# opensda-shield.net
KiCad netlist of a schematic drawn in EAGLE
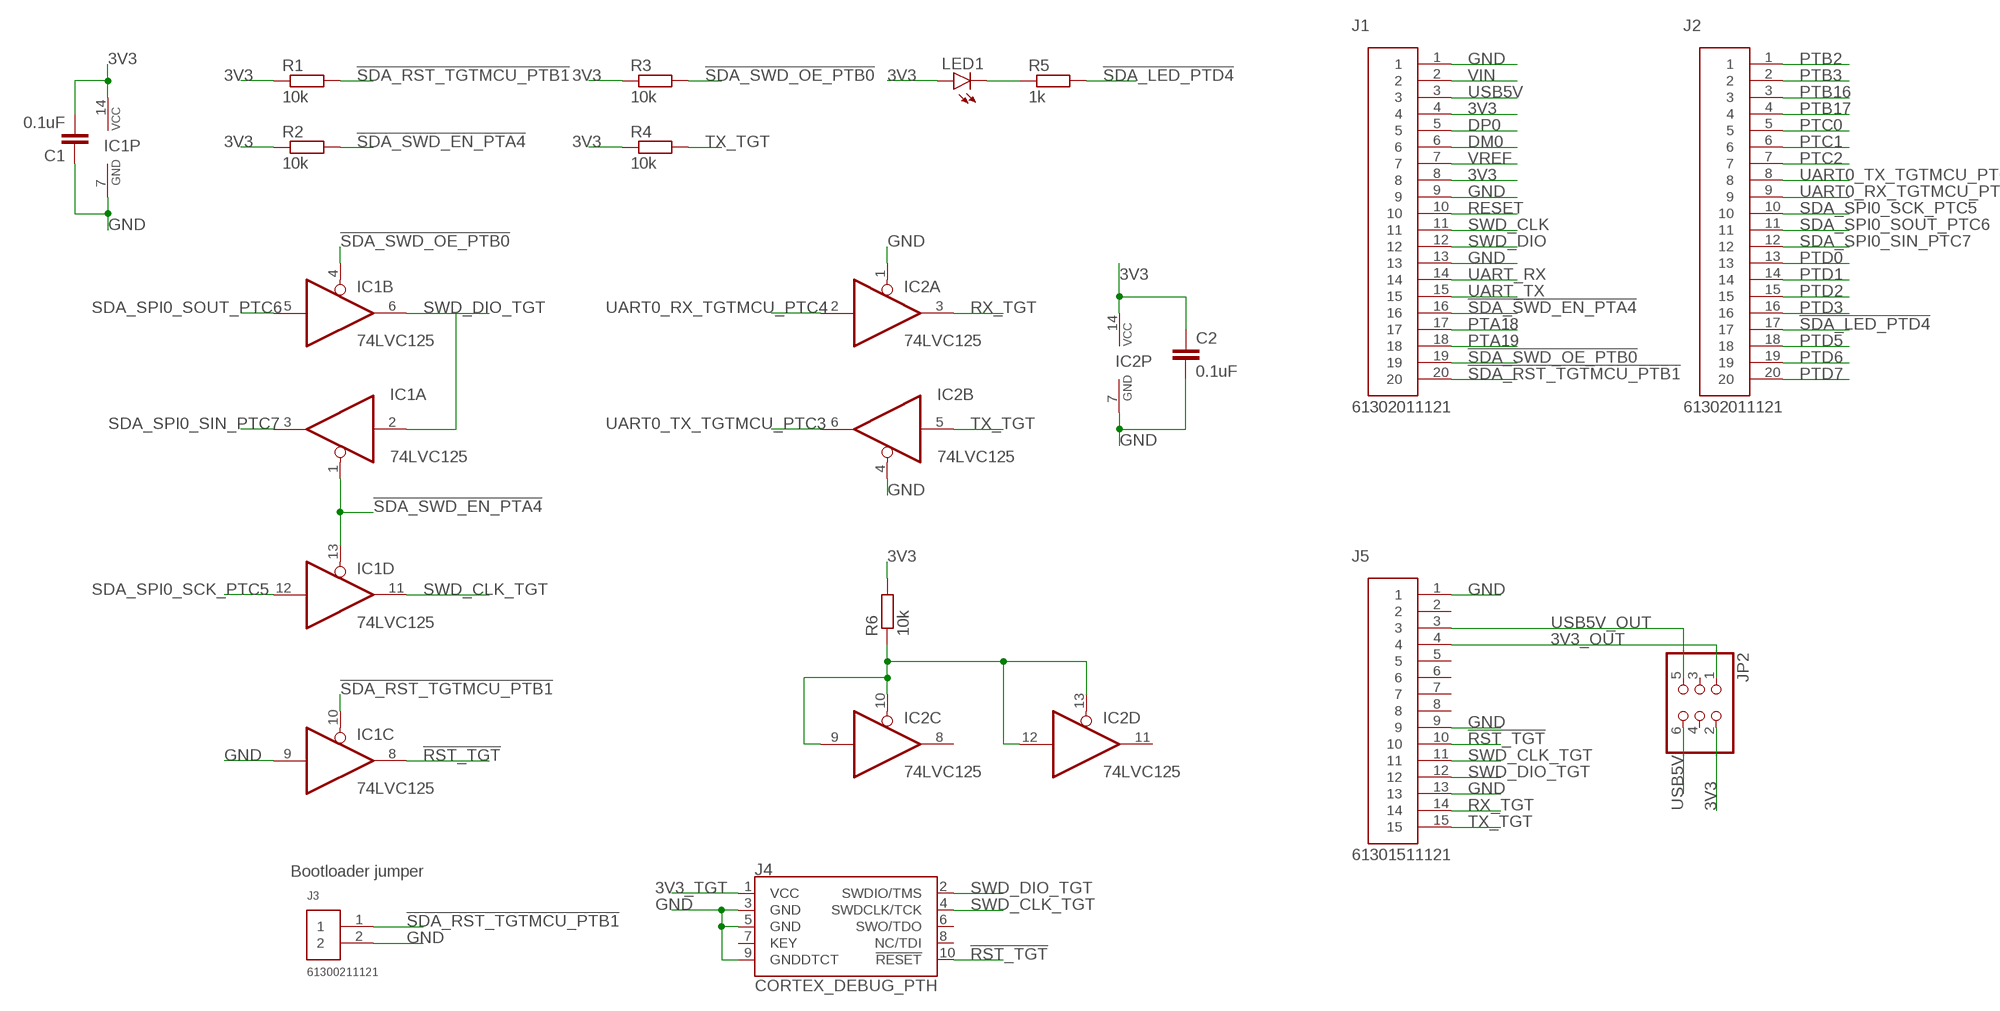
[diagram p0: schematic, sheet 1]

(export (version "E")
  (design (tool "Eeschema 10.0.6"))
  (components
    (comp (ref "C1")
      (value "0.1uF")
      (footprint "eagle-import:C0805")
      (libsource (lib "eagle-import") (part "C-EUC0805"))
    )
    (comp (ref "C2")
      (value "0.1uF")
      (footprint "eagle-import:C0805")
      (libsource (lib "eagle-import") (part "C-EUC0805"))
    )
    (comp (ref "IC1")
      (value "74LVC125")
      (footprint "eagle-import:TSSOP14")
      (libsource (lib "eagle-import") (part "74125PWABT"))
    )
    (comp (ref "IC2")
      (value "74LVC125")
      (footprint "eagle-import:TSSOP14")
      (libsource (lib "eagle-import") (part "74125PWABT"))
    )
    (comp (ref "J1")
      (value "61302011121")
      (footprint "eagle-import:61302011121")
      (fields
        (field (name "DIGIKEY_PART_NUMBER") "732-5329-ND")
        (field (name "MANUFACTURER") "Wurth Electronics Inc.")
        (field (name "CREATED_BY") "PCBLayout.com")
      )
      (libsource (lib "eagle-import") (part "61302011121"))
    )
    (comp (ref "J2")
      (value "61302011121")
      (footprint "eagle-import:61302011121")
      (fields
        (field (name "DIGIKEY_PART_NUMBER") "732-5329-ND")
        (field (name "MANUFACTURER") "Wurth Electronics Inc.")
        (field (name "CREATED_BY") "PCBLayout.com")
      )
      (libsource (lib "eagle-import") (part "61302011121"))
    )
    (comp (ref "J3")
      (value "61300211121")
      (footprint "eagle-import:61300211121")
      (fields
        (field (name "DIGI_KEY_PART_NUMBER") "732-5315-ND")
        (field (name "MANUFACTURER") "Wurth Electronics Inc.")
        (field (name "CREATED_BY") "PCBLayout.com")
      )
      (libsource (lib "eagle-import") (part "61300211121"))
    )
    (comp (ref "J4")
      (value "CORTEX_DEBUG_PTH")
      (footprint "eagle-import:2X5-PTH-1.27MM")
      (libsource (lib "eagle-import") (part "CORTEX_DEBUG_PTH"))
    )
    (comp (ref "J5")
      (value "61301511121")
      (footprint "eagle-import:61301511121")
      (fields
        (field (name "DIGIKEY_PART_NUMBER") "732-5326-ND")
        (field (name "MANUFACTURER") "Wurth Electronics Inc.")
        (field (name "CREATED_BY") "PCBLayout.com")
      )
      (libsource (lib "eagle-import") (part "61301511121"))
    )
    (comp (ref "JP2")
      (value "PINHD-2X3")
      (footprint "eagle-import:2X03")
      (libsource (lib "eagle-import") (part "PINHD-2X3"))
    )
    (comp (ref "LED1")
      (value "LEDCHIPLED_0805")
      (footprint "eagle-import:CHIPLED_0805")
      (libsource (lib "eagle-import") (part "LEDCHIPLED_0805"))
    )
    (comp (ref "R1")
      (value "10k")
      (footprint "eagle-import:R0805")
      (libsource (lib "eagle-import") (part "R-EU_R0805"))
    )
    (comp (ref "R2")
      (value "10k")
      (footprint "eagle-import:R0805")
      (libsource (lib "eagle-import") (part "R-EU_R0805"))
    )
    (comp (ref "R3")
      (value "10k")
      (footprint "eagle-import:R0805")
      (libsource (lib "eagle-import") (part "R-EU_R0805"))
    )
    (comp (ref "R4")
      (value "10k")
      (footprint "eagle-import:R0805")
      (libsource (lib "eagle-import") (part "R-EU_R0805"))
    )
    (comp (ref "R5")
      (value "1k")
      (footprint "eagle-import:R0805")
      (libsource (lib "eagle-import") (part "R-EU_R0805"))
    )
    (comp (ref "R6")
      (value "10k")
      (footprint "eagle-import:R0805")
      (libsource (lib "eagle-import") (part "R-EU_R0805"))
    )
  )
  (nets
    (net (code "1") (name "/3V3") (class "Default")
      (node (ref "C1") (pin "2") (pinfunction "2_2") (pintype "passive"))
      (node (ref "C2") (pin "1") (pinfunction "1_1") (pintype "passive"))
      (node (ref "IC1") (pin "14") (pinfunction "VCC_14") (pintype "power_in"))
      (node (ref "IC2") (pin "14") (pinfunction "VCC_14") (pintype "power_in"))
      (node (ref "J1") (pin "4") (pinfunction "4_4") (pintype "passive"))
      (node (ref "J1") (pin "8") (pinfunction "8_8") (pintype "passive"))
      (node (ref "JP2") (pin "2") (pinfunction "2_2") (pintype "passive"))
      (node (ref "LED1") (pin "A") (pinfunction "A_A") (pintype "passive"))
      (node (ref "R1") (pin "1") (pinfunction "1_1") (pintype "passive"))
      (node (ref "R2") (pin "1") (pinfunction "1_1") (pintype "passive"))
      (node (ref "R3") (pin "1") (pinfunction "1_1") (pintype "passive"))
      (node (ref "R4") (pin "1") (pinfunction "1_1") (pintype "passive"))
      (node (ref "R6") (pin "2") (pinfunction "2_2") (pintype "passive"))
    )
    (net (code "2") (name "/3V3_OUT") (class "Default")
      (node (ref "J5") (pin "4") (pinfunction "4_4") (pintype "passive"))
      (node (ref "JP2") (pin "1") (pinfunction "1_1") (pintype "passive"))
    )
    (net (code "3") (name "/3V3_TGT") (class "Default")
      (node (ref "J4") (pin "1") (pinfunction "VCC_1") (pintype "bidirectional"))
    )
    (net (code "4") (name "/DM0") (class "Default")
      (node (ref "J1") (pin "6") (pinfunction "6_6") (pintype "passive"))
    )
    (net (code "5") (name "/DP0") (class "Default")
      (node (ref "J1") (pin "5") (pinfunction "5_5") (pintype "passive"))
    )
    (net (code "6") (name "/GND") (class "Default")
      (node (ref "C1") (pin "1") (pinfunction "1_1") (pintype "passive"))
      (node (ref "C2") (pin "2") (pinfunction "2_2") (pintype "passive"))
      (node (ref "IC1") (pin "7") (pinfunction "GND_7") (pintype "power_in"))
      (node (ref "IC1") (pin "9") (pinfunction "I_9") (pintype "input"))
      (node (ref "IC2") (pin "1") (pinfunction "OE_1") (pintype "input"))
      (node (ref "IC2") (pin "4") (pinfunction "OE_4") (pintype "input"))
      (node (ref "IC2") (pin "7") (pinfunction "GND_7") (pintype "power_in"))
      (node (ref "J1") (pin "1") (pinfunction "1_1") (pintype "passive"))
      (node (ref "J1") (pin "13") (pinfunction "13_13") (pintype "passive"))
      (node (ref "J1") (pin "9") (pinfunction "9_9") (pintype "passive"))
      (node (ref "J3") (pin "2") (pinfunction "2_2") (pintype "passive"))
      (node (ref "J4") (pin "3") (pinfunction "GND_3") (pintype "bidirectional"))
      (node (ref "J4") (pin "5") (pinfunction "GND_5") (pintype "bidirectional"))
      (node (ref "J4") (pin "9") (pinfunction "GNDDTCT_9") (pintype "bidirectional"))
      (node (ref "J5") (pin "1") (pinfunction "1_1") (pintype "passive"))
      (node (ref "J5") (pin "13") (pinfunction "13_13") (pintype "passive"))
      (node (ref "J5") (pin "9") (pinfunction "9_9") (pintype "passive"))
    )
    (net (code "7") (name "/PTA18") (class "Default")
      (node (ref "J1") (pin "17") (pinfunction "17_17") (pintype "passive"))
    )
    (net (code "8") (name "/PTA19") (class "Default")
      (node (ref "J1") (pin "18") (pinfunction "18_18") (pintype "passive"))
    )
    (net (code "9") (name "/PTB2") (class "Default")
      (node (ref "J2") (pin "1") (pinfunction "1_1") (pintype "passive"))
    )
    (net (code "10") (name "/PTB3") (class "Default")
      (node (ref "J2") (pin "2") (pinfunction "2_2") (pintype "passive"))
    )
    (net (code "11") (name "/PTB16") (class "Default")
      (node (ref "J2") (pin "3") (pinfunction "3_3") (pintype "passive"))
    )
    (net (code "12") (name "/PTB17") (class "Default")
      (node (ref "J2") (pin "4") (pinfunction "4_4") (pintype "passive"))
    )
    (net (code "13") (name "/PTC0") (class "Default")
      (node (ref "J2") (pin "5") (pinfunction "5_5") (pintype "passive"))
    )
    (net (code "14") (name "/PTC1") (class "Default")
      (node (ref "J2") (pin "6") (pinfunction "6_6") (pintype "passive"))
    )
    (net (code "15") (name "/PTC2") (class "Default")
      (node (ref "J2") (pin "7") (pinfunction "7_7") (pintype "passive"))
    )
    (net (code "16") (name "/PTD0") (class "Default")
      (node (ref "J2") (pin "13") (pinfunction "13_13") (pintype "passive"))
    )
    (net (code "17") (name "/PTD1") (class "Default")
      (node (ref "J2") (pin "14") (pinfunction "14_14") (pintype "passive"))
    )
    (net (code "18") (name "/PTD2") (class "Default")
      (node (ref "J2") (pin "15") (pinfunction "15_15") (pintype "passive"))
    )
    (net (code "19") (name "/PTD3") (class "Default")
      (node (ref "J2") (pin "16") (pinfunction "16_16") (pintype "passive"))
    )
    (net (code "20") (name "/PTD5") (class "Default")
      (node (ref "J2") (pin "18") (pinfunction "18_18") (pintype "passive"))
    )
    (net (code "21") (name "/PTD6") (class "Default")
      (node (ref "J2") (pin "19") (pinfunction "19_19") (pintype "passive"))
    )
    (net (code "22") (name "/PTD7") (class "Default")
      (node (ref "J2") (pin "20") (pinfunction "20_20") (pintype "passive"))
    )
    (net (code "23") (name "/RESET") (class "Default")
      (node (ref "J1") (pin "10") (pinfunction "10_10") (pintype "passive"))
    )
    (net (code "24") (name "/RX_TGT") (class "Default")
      (node (ref "IC2") (pin "3") (pinfunction "O_3") (pintype "tri_state"))
      (node (ref "J5") (pin "14") (pinfunction "14_14") (pintype "passive"))
    )
    (net (code "25") (name "/SDA_SPI0_SCK_PTC5") (class "Default")
      (node (ref "IC1") (pin "12") (pinfunction "I_12") (pintype "input"))
      (node (ref "J2") (pin "10") (pinfunction "10_10") (pintype "passive"))
    )
    (net (code "26") (name "/SDA_SPI0_SIN_PTC7") (class "Default")
      (node (ref "IC1") (pin "3") (pinfunction "O_3") (pintype "tri_state"))
      (node (ref "J2") (pin "12") (pinfunction "12_12") (pintype "passive"))
    )
    (net (code "27") (name "/SDA_SPI0_SOUT_PTC6") (class "Default")
      (node (ref "IC1") (pin "5") (pinfunction "I_5") (pintype "input"))
      (node (ref "J2") (pin "11") (pinfunction "11_11") (pintype "passive"))
    )
    (net (code "28") (name "/SWD_CLK") (class "Default")
      (node (ref "J1") (pin "11") (pinfunction "11_11") (pintype "passive"))
    )
    (net (code "29") (name "/SWD_CLK_TGT") (class "Default")
      (node (ref "IC1") (pin "11") (pinfunction "O_11") (pintype "tri_state"))
      (node (ref "J4") (pin "4") (pinfunction "SWDCLK/TCK_4") (pintype "bidirectional"))
      (node (ref "J5") (pin "11") (pinfunction "11_11") (pintype "passive"))
    )
    (net (code "30") (name "/SWD_DIO") (class "Default")
      (node (ref "J1") (pin "12") (pinfunction "12_12") (pintype "passive"))
    )
    (net (code "31") (name "/SWD_DIO_TGT") (class "Default")
      (node (ref "IC1") (pin "2") (pinfunction "I_2") (pintype "input"))
      (node (ref "IC1") (pin "6") (pinfunction "O_6") (pintype "tri_state"))
      (node (ref "J4") (pin "2") (pinfunction "SWDIO/TMS_2") (pintype "bidirectional"))
      (node (ref "J5") (pin "12") (pinfunction "12_12") (pintype "passive"))
    )
    (net (code "32") (name "/TX_TGT") (class "Default")
      (node (ref "IC2") (pin "5") (pinfunction "I_5") (pintype "input"))
      (node (ref "J5") (pin "15") (pinfunction "15_15") (pintype "passive"))
      (node (ref "R4") (pin "2") (pinfunction "2_2") (pintype "passive"))
    )
    (net (code "33") (name "/UART0_RX_TGTMCU_PTC4") (class "Default")
      (node (ref "IC2") (pin "2") (pinfunction "I_2") (pintype "input"))
      (node (ref "J2") (pin "9") (pinfunction "9_9") (pintype "passive"))
    )
    (net (code "34") (name "/UART0_TX_TGTMCU_PTC3") (class "Default")
      (node (ref "IC2") (pin "6") (pinfunction "O_6") (pintype "tri_state"))
      (node (ref "J2") (pin "8") (pinfunction "8_8") (pintype "passive"))
    )
    (net (code "35") (name "/UART_RX") (class "Default")
      (node (ref "J1") (pin "14") (pinfunction "14_14") (pintype "passive"))
    )
    (net (code "36") (name "/UART_TX") (class "Default")
      (node (ref "J1") (pin "15") (pinfunction "15_15") (pintype "passive"))
    )
    (net (code "37") (name "/USB5V") (class "Default")
      (node (ref "J1") (pin "3") (pinfunction "3_3") (pintype "passive"))
      (node (ref "JP2") (pin "6") (pinfunction "6_6") (pintype "passive"))
    )
    (net (code "38") (name "/USB5V_OUT") (class "Default")
      (node (ref "J5") (pin "3") (pinfunction "3_3") (pintype "passive"))
      (node (ref "JP2") (pin "5") (pinfunction "5_5") (pintype "passive"))
    )
    (net (code "39") (name "/VIN") (class "Default")
      (node (ref "J1") (pin "2") (pinfunction "2_2") (pintype "passive"))
    )
    (net (code "40") (name "/VREF") (class "Default")
      (node (ref "J1") (pin "7") (pinfunction "7_7") (pintype "passive"))
    )
    (net (code "41") (name "/~{RST_TGT}") (class "Default")
      (node (ref "IC1") (pin "8") (pinfunction "O_8") (pintype "tri_state"))
      (node (ref "J4") (pin "10") (pinfunction "~{RESET}_10") (pintype "bidirectional"))
      (node (ref "J5") (pin "10") (pinfunction "10_10") (pintype "passive"))
    )
    (net (code "42") (name "/~{SDA_LED_PTD4}") (class "Default")
      (node (ref "J2") (pin "17") (pinfunction "17_17") (pintype "passive"))
      (node (ref "R5") (pin "2") (pinfunction "2_2") (pintype "passive"))
    )
    (net (code "43") (name "/~{SDA_RST_TGTMCU_PTB1}") (class "Default")
      (node (ref "IC1") (pin "10") (pinfunction "OE_10") (pintype "input"))
      (node (ref "J1") (pin "20") (pinfunction "20_20") (pintype "passive"))
      (node (ref "J3") (pin "1") (pinfunction "1_1") (pintype "passive"))
      (node (ref "R1") (pin "2") (pinfunction "2_2") (pintype "passive"))
    )
    (net (code "44") (name "/~{SDA_SWD_EN_PTA4}") (class "Default")
      (node (ref "IC1") (pin "1") (pinfunction "OE_1") (pintype "input"))
      (node (ref "IC1") (pin "13") (pinfunction "OE_13") (pintype "input"))
      (node (ref "J1") (pin "16") (pinfunction "16_16") (pintype "passive"))
      (node (ref "R2") (pin "2") (pinfunction "2_2") (pintype "passive"))
    )
    (net (code "45") (name "/~{SDA_SWD_OE_PTB0}") (class "Default")
      (node (ref "IC1") (pin "4") (pinfunction "OE_4") (pintype "input"))
      (node (ref "J1") (pin "19") (pinfunction "19_19") (pintype "passive"))
      (node (ref "R3") (pin "2") (pinfunction "2_2") (pintype "passive"))
    )
    (net (code "46") (name "Net-(IC2C-I)") (class "Default")
      (node (ref "IC2") (pin "10") (pinfunction "OE_10") (pintype "input"))
      (node (ref "IC2") (pin "12") (pinfunction "I_12") (pintype "input"))
      (node (ref "IC2") (pin "13") (pinfunction "OE_13") (pintype "input"))
      (node (ref "IC2") (pin "9") (pinfunction "I_9") (pintype "input"))
      (node (ref "R6") (pin "1") (pinfunction "1_1") (pintype "passive"))
    )
    (net (code "47") (name "Net-(LED1-PadC)") (class "Default")
      (node (ref "LED1") (pin "C") (pinfunction "C_C") (pintype "passive"))
      (node (ref "R5") (pin "1") (pinfunction "1_1") (pintype "passive"))
    )
    (net (code "48") (name "unconnected-(IC2C-O-Pad8)") (class "Default")
      (node (ref "IC2") (pin "8") (pinfunction "O_8") (pintype "tri_state"))
    )
    (net (code "49") (name "unconnected-(IC2D-O-Pad11)") (class "Default")
      (node (ref "IC2") (pin "11") (pinfunction "O_11") (pintype "tri_state"))
    )
    (net (code "50") (name "unconnected-(J4-KEY-Pad7)") (class "Default")
      (node (ref "J4") (pin "7") (pinfunction "KEY_7") (pintype "bidirectional"))
    )
    (net (code "51") (name "unconnected-(J4-NC{slash}TDI-Pad8)") (class "Default")
      (node (ref "J4") (pin "8") (pinfunction "NC/TDI_8") (pintype "bidirectional"))
    )
    (net (code "52") (name "unconnected-(J4-SWO{slash}TDO-Pad6)") (class "Default")
      (node (ref "J4") (pin "6") (pinfunction "SWO/TDO_6") (pintype "bidirectional"))
    )
    (net (code "53") (name "unconnected-(J5-Pad2)") (class "Default")
      (node (ref "J5") (pin "2") (pinfunction "2_2") (pintype "passive"))
    )
    (net (code "54") (name "unconnected-(J5-Pad5)") (class "Default")
      (node (ref "J5") (pin "5") (pinfunction "5_5") (pintype "passive"))
    )
    (net (code "55") (name "unconnected-(J5-Pad6)") (class "Default")
      (node (ref "J5") (pin "6") (pinfunction "6_6") (pintype "passive"))
    )
    (net (code "56") (name "unconnected-(J5-Pad7)") (class "Default")
      (node (ref "J5") (pin "7") (pinfunction "7_7") (pintype "passive"))
    )
    (net (code "57") (name "unconnected-(J5-Pad8)") (class "Default")
      (node (ref "J5") (pin "8") (pinfunction "8_8") (pintype "passive"))
    )
    (net (code "58") (name "unconnected-(JP2-Pad3)") (class "Default")
      (node (ref "JP2") (pin "3") (pinfunction "3_3") (pintype "passive"))
    )
    (net (code "59") (name "unconnected-(JP2-Pad4)") (class "Default")
      (node (ref "JP2") (pin "4") (pinfunction "4_4") (pintype "passive"))
    )
  )
)
